# schematic.net
KiCad netlist of a schematic drawn in Altium Designer
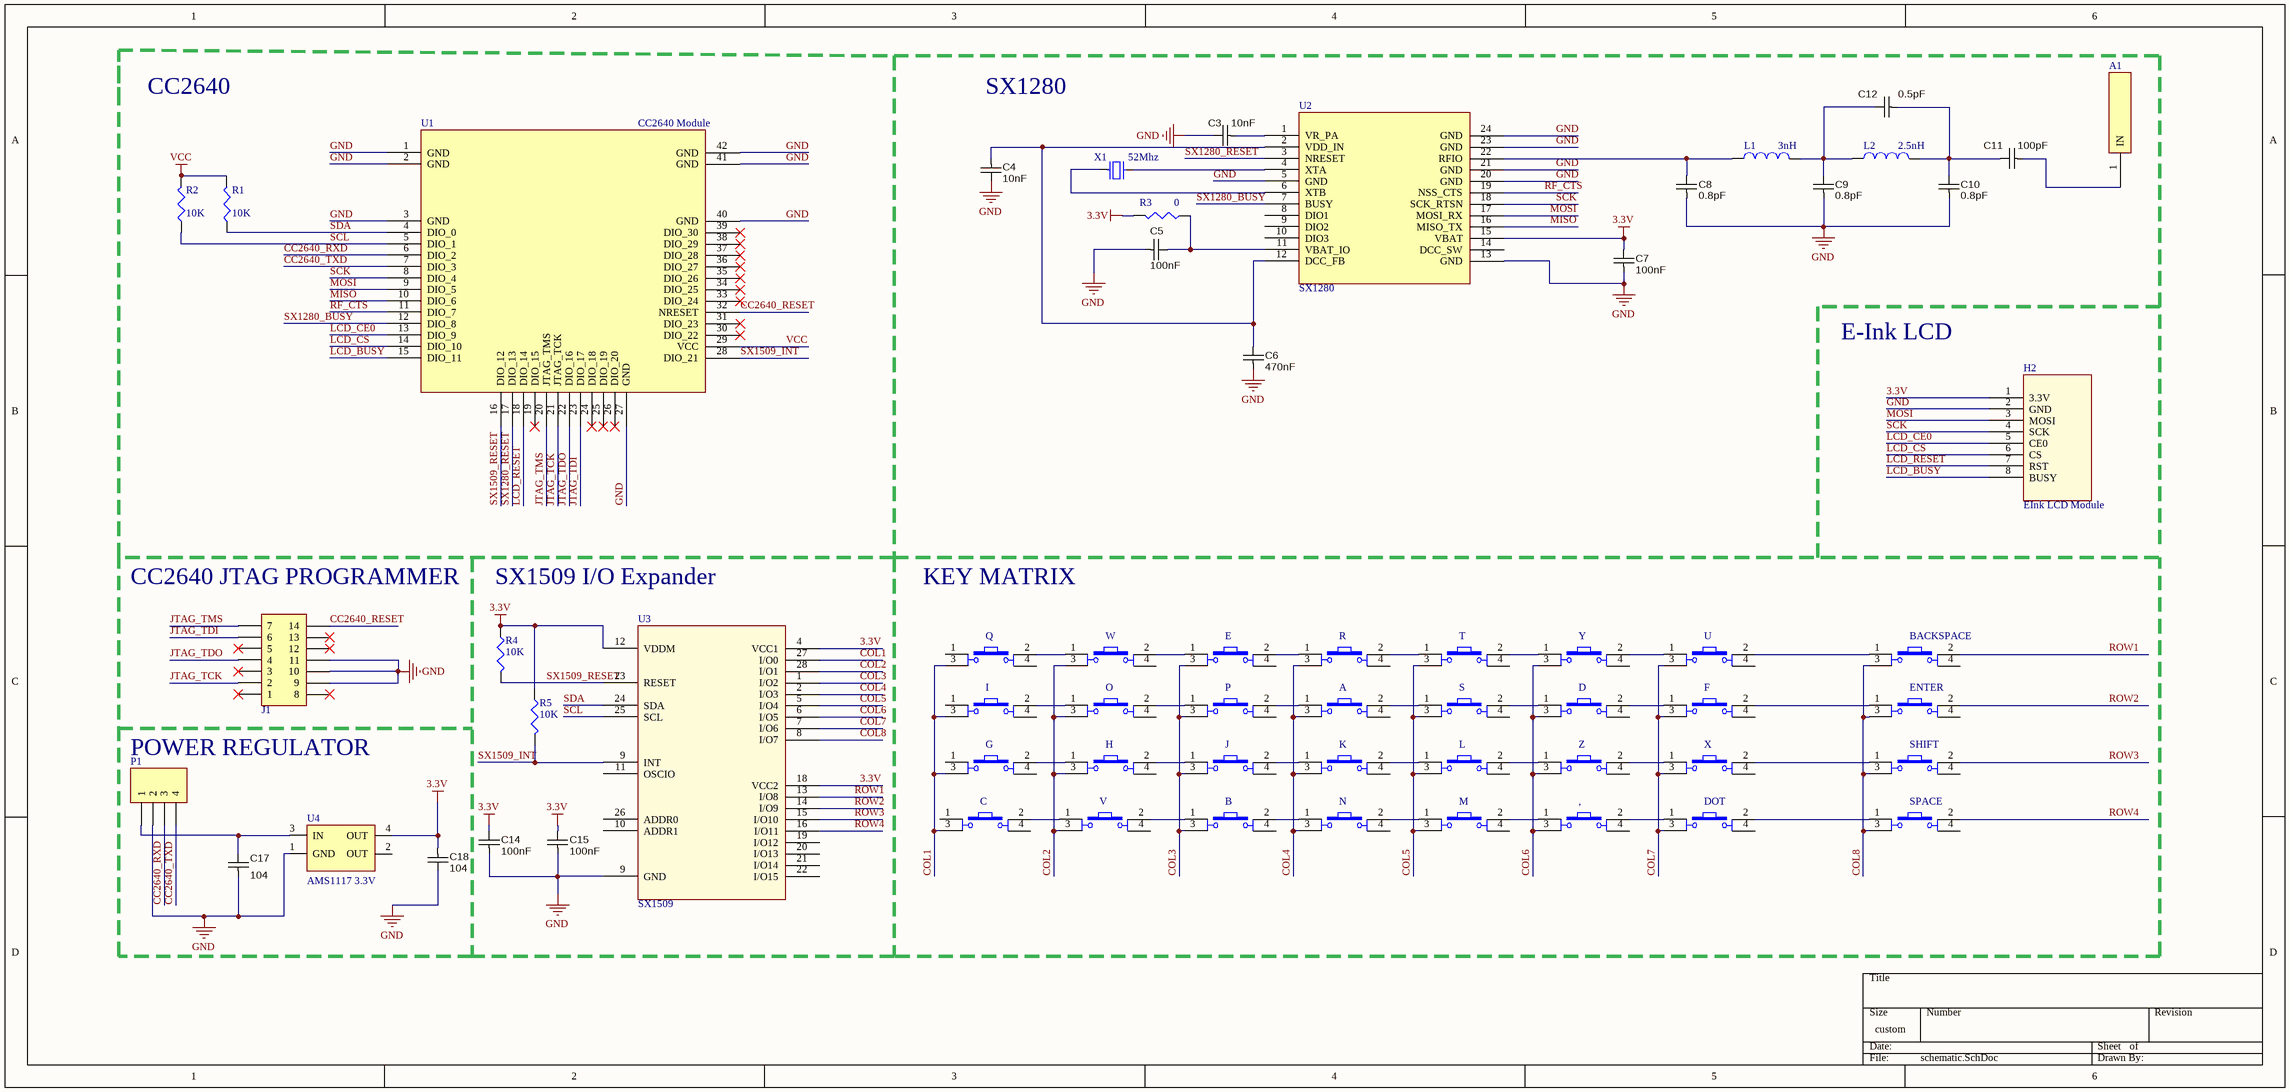
[diagram p0: schematic.SchDoc]

(export (version "E")
  (design (tool "Eeschema 10.0.6"))
  (components
    (comp (ref ",")
      (value "SW")
      (footprint "Kha_Button")
      (description "Switch button 4 pin")
      (libsource (lib "syhaunguyen") (part "SW4"))
    )
    (comp (ref "A")
      (value "SW")
      (footprint "Kha_Button")
      (description "Switch button 4 pin")
      (libsource (lib "syhaunguyen") (part "SW4"))
    )
    (comp (ref "A1")
      (value "Antenna")
      (footprint "Antenna")
      (libsource (lib "EInk_Project_Lib") (part "Antenna"))
    )
    (comp (ref "B")
      (value "SW")
      (footprint "Kha_Button")
      (description "Switch button 4 pin")
      (libsource (lib "syhaunguyen") (part "SW4"))
    )
    (comp (ref "BACKSPACE")
      (value "SW")
      (footprint "Kha_Button")
      (description "Switch button 4 pin")
      (libsource (lib "syhaunguyen") (part "SW4"))
    )
    (comp (ref "C")
      (value "SW")
      (footprint "Kha_Button")
      (description "Switch button 4 pin")
      (libsource (lib "syhaunguyen") (part "SW4"))
    )
    (comp (ref "C3")
      (value "10nF")
      (footprint "SMD-0603c")
      (description "Capacitor SMD Cer 1nF 10% 100V X7R 0603")
      (fields (field (name "TOLERANCE") "±10%") (field (name "Comment") "approved sub OK"))
      (libsource (lib "PBL - Capacitors") (part "CAPC_1n_0603_X7R_100V_10%"))
    )
    (comp (ref "C4")
      (value "10nF")
      (footprint "SMD-0603c")
      (description "Capacitor SMD Cer 1nF 10% 100V X7R 0603")
      (fields (field (name "TOLERANCE") "±10%") (field (name "Comment") "approved sub OK"))
      (libsource (lib "PBL - Capacitors") (part "CAPC_1n_0603_X7R_100V_10%"))
    )
    (comp (ref "C5")
      (value "100nF")
      (footprint "SMD-0603c")
      (description "Capacitor SMD Cer 1nF 10% 100V X7R 0603")
      (fields (field (name "TOLERANCE") "±10%") (field (name "Comment") "approved sub OK"))
      (libsource (lib "PBL - Capacitors") (part "CAPC_1n_0603_X7R_100V_10%"))
    )
    (comp (ref "C6")
      (value "470nF")
      (footprint "SMD-0603c")
      (description "Capacitor SMD Cer 1nF 10% 100V X7R 0603")
      (fields (field (name "TOLERANCE") "±10%") (field (name "Comment") "approved sub OK"))
      (libsource (lib "PBL - Capacitors") (part "CAPC_1n_0603_X7R_100V_10%"))
    )
    (comp (ref "C7")
      (value "100nF")
      (footprint "SMD-0603c")
      (description "Capacitor SMD Cer 1nF 10% 100V X7R 0603")
      (fields (field (name "TOLERANCE") "±10%") (field (name "Comment") "approved sub OK"))
      (libsource (lib "PBL - Capacitors") (part "CAPC_1n_0603_X7R_100V_10%"))
    )
    (comp (ref "C8")
      (value "0.8pF")
      (footprint "SMD-0603c")
      (description "Capacitor SMD Cer 1nF 10% 100V X7R 0603")
      (fields (field (name "TOLERANCE") "±10%") (field (name "Comment") "approved sub OK"))
      (libsource (lib "PBL - Capacitors") (part "CAPC_1n_0603_X7R_100V_10%"))
    )
    (comp (ref "C9")
      (value "0.8pF")
      (footprint "SMD-0603c")
      (description "Capacitor SMD Cer 1nF 10% 100V X7R 0603")
      (fields (field (name "TOLERANCE") "±10%") (field (name "Comment") "approved sub OK"))
      (libsource (lib "PBL - Capacitors") (part "CAPC_1n_0603_X7R_100V_10%"))
    )
    (comp (ref "C10")
      (value "0.8pF")
      (footprint "SMD-0603c")
      (description "Capacitor SMD Cer 1nF 10% 100V X7R 0603")
      (fields (field (name "TOLERANCE") "±10%") (field (name "Comment") "approved sub OK"))
      (libsource (lib "PBL - Capacitors") (part "CAPC_1n_0603_X7R_100V_10%"))
    )
    (comp (ref "C11")
      (value "100pF")
      (footprint "SMD-0603c")
      (description "Capacitor SMD Cer 1nF 10% 100V X7R 0603")
      (fields (field (name "TOLERANCE") "±10%") (field (name "Comment") "approved sub OK"))
      (libsource (lib "PBL - Capacitors") (part "CAPC_1n_0603_X7R_100V_10%"))
    )
    (comp (ref "C12")
      (value "0.5pF")
      (footprint "SMD-0603c")
      (description "Capacitor SMD Cer 1nF 10% 100V X7R 0603")
      (fields (field (name "TOLERANCE") "±10%") (field (name "Comment") "approved sub OK"))
      (libsource (lib "PBL - Capacitors") (part "CAPC_1n_0603_X7R_100V_10%"))
    )
    (comp (ref "C14")
      (value "100nF")
      (footprint "SMD-0603c")
      (description "Capacitor SMD Cer 1nF 10% 100V X7R 0603")
      (fields (field (name "TOLERANCE") "±10%") (field (name "Comment") "approved sub OK"))
      (libsource (lib "PBL - Capacitors") (part "CAPC_1n_0603_X7R_100V_10%"))
    )
    (comp (ref "C15")
      (value "100nF")
      (footprint "SMD-0603c")
      (description "Capacitor SMD Cer 1nF 10% 100V X7R 0603")
      (fields (field (name "TOLERANCE") "±10%") (field (name "Comment") "approved sub OK"))
      (libsource (lib "PBL - Capacitors") (part "CAPC_1n_0603_X7R_100V_10%"))
    )
    (comp (ref "C17")
      (value "104")
      (footprint "SMD-0603c")
      (description "Capacitor SMD Cer 1nF 10% 100V X7R 0603")
      (fields (field (name "TOLERANCE") "±10%") (field (name "Comment") "approved sub OK"))
      (libsource (lib "PBL - Capacitors") (part "CAPC_1n_0603_X7R_100V_10%"))
    )
    (comp (ref "C18")
      (value "104")
      (footprint "SMD-0603c")
      (description "Capacitor SMD Cer 1nF 10% 100V X7R 0603")
      (fields (field (name "TOLERANCE") "±10%") (field (name "Comment") "approved sub OK"))
      (libsource (lib "PBL - Capacitors") (part "CAPC_1n_0603_X7R_100V_10%"))
    )
    (comp (ref "D")
      (value "SW")
      (footprint "Kha_Button")
      (description "Switch button 4 pin")
      (libsource (lib "syhaunguyen") (part "SW4"))
    )
    (comp (ref "DOT")
      (value "SW")
      (footprint "Kha_Button")
      (description "Switch button 4 pin")
      (libsource (lib "syhaunguyen") (part "SW4"))
    )
    (comp (ref "E")
      (value "SW")
      (footprint "Kha_Button")
      (description "Switch button 4 pin")
      (libsource (lib "syhaunguyen") (part "SW4"))
    )
    (comp (ref "ENTER")
      (value "SW")
      (footprint "Kha_Button")
      (description "Switch button 4 pin")
      (libsource (lib "syhaunguyen") (part "SW4"))
    )
    (comp (ref "F")
      (value "SW")
      (footprint "Kha_Button")
      (description "Switch button 4 pin")
      (libsource (lib "syhaunguyen") (part "SW4"))
    )
    (comp (ref "G")
      (value "SW")
      (footprint "Kha_Button")
      (description "Switch button 4 pin")
      (libsource (lib "syhaunguyen") (part "SW4"))
    )
    (comp (ref "H")
      (value "SW")
      (footprint "Kha_Button")
      (description "Switch button 4 pin")
      (libsource (lib "syhaunguyen") (part "SW4"))
    )
    (comp (ref "H2")
      (value "EInk LCD Module")
      (footprint "EInk_Module")
      (libsource (lib "EInk_Project_Lib") (part "E-Ink LCD"))
    )
    (comp (ref "I")
      (value "SW")
      (footprint "Kha_Button")
      (description "Switch button 4 pin")
      (libsource (lib "syhaunguyen") (part "SW4"))
    )
    (comp (ref "J")
      (value "SW")
      (footprint "Kha_Button")
      (description "Switch button 4 pin")
      (libsource (lib "syhaunguyen") (part "SW4"))
    )
    (comp (ref "J1")
      (value "14p")
      (footprint "610114249121")
      (description "WR-PHD 2.54 mm Pin Header - SMT Type Double Row Right Angled, 14p")
      (fields (field (name "PARTNUMBER") "610114249121") (field (name "PUBLISHER") "Wurth Elektronik"))
      (libsource (lib "ALTIUM-PHD_2_54_SMT_DOUBLE_ROW_RIGHT_ANGLED_PIN_HEADER_6101XX249121-rev16c") (part "610114249121"))
    )
    (comp (ref "K")
      (value "SW")
      (footprint "Kha_Button")
      (description "Switch button 4 pin")
      (libsource (lib "syhaunguyen") (part "SW4"))
    )
    (comp (ref "L")
      (value "SW")
      (footprint "Kha_Button")
      (description "Switch button 4 pin")
      (libsource (lib "syhaunguyen") (part "SW4"))
    )
    (comp (ref "L1")
      (value "3nH")
      (footprint "0603")
      (description "Inductor")
      (fields (field (name "PUBLISHER") "Altium Limited"))
      (libsource (lib "Miscellaneous Devices") (part "Inductor"))
    )
    (comp (ref "L2")
      (value "2.5nH")
      (footprint "0603")
      (description "Inductor")
      (fields (field (name "PUBLISHER") "Altium Limited"))
      (libsource (lib "Miscellaneous Devices") (part "Inductor"))
    )
    (comp (ref "M")
      (value "SW")
      (footprint "Kha_Button")
      (description "Switch button 4 pin")
      (libsource (lib "syhaunguyen") (part "SW4"))
    )
    (comp (ref "N")
      (value "SW")
      (footprint "Kha_Button")
      (description "Switch button 4 pin")
      (libsource (lib "syhaunguyen") (part "SW4"))
    )
    (comp (ref "O")
      (value "SW")
      (footprint "Kha_Button")
      (description "Switch button 4 pin")
      (libsource (lib "syhaunguyen") (part "SW4"))
    )
    (comp (ref "P")
      (value "SW")
      (footprint "Kha_Button")
      (description "Switch button 4 pin")
      (libsource (lib "syhaunguyen") (part "SW4"))
    )
    (comp (ref "P1")
      (value "Header 4")
      (footprint "Header 4 SMT")
      (description "Header, 4-Pin")
      (fields (field (name "PUBLISHER") "Altium Limited"))
      (libsource (lib "Miscellaneous Connectors") (part "Header 4"))
    )
    (comp (ref "Q")
      (value "SW")
      (footprint "Kha_Button")
      (description "Switch button 4 pin")
      (libsource (lib "syhaunguyen") (part "SW4"))
    )
    (comp (ref "R")
      (value "SW")
      (footprint "Kha_Button")
      (description "Switch button 4 pin")
      (libsource (lib "syhaunguyen") (part "SW4"))
    )
    (comp (ref "R1")
      (value "10K")
      (footprint "J1-0603")
      (description "Resistor")
      (fields (field (name "Comment") "Res3") (field (name "PUBLISHER") "Altium Limited"))
      (libsource (lib "Miscellaneous Devices") (part "Res3"))
    )
    (comp (ref "R2")
      (value "10K")
      (footprint "J1-0603")
      (description "Resistor")
      (fields (field (name "Comment") "Res3") (field (name "PUBLISHER") "Altium Limited"))
      (libsource (lib "Miscellaneous Devices") (part "Res3"))
    )
    (comp (ref "R3")
      (value "0")
      (footprint "J1-0603")
      (description "Resistor")
      (fields (field (name "Comment") "Res3") (field (name "PUBLISHER") "Altium Limited"))
      (libsource (lib "Miscellaneous Devices") (part "Res3"))
    )
    (comp (ref "R4")
      (value "10K")
      (footprint "J1-0603")
      (description "Resistor")
      (fields (field (name "Comment") "Res3") (field (name "PUBLISHER") "Altium Limited"))
      (libsource (lib "Miscellaneous Devices") (part "Res3"))
    )
    (comp (ref "R5")
      (value "10K")
      (footprint "J1-0603")
      (description "Resistor")
      (fields (field (name "Comment") "Res3") (field (name "PUBLISHER") "Altium Limited"))
      (libsource (lib "Miscellaneous Devices") (part "Res3"))
    )
    (comp (ref "S")
      (value "SW")
      (footprint "Kha_Button")
      (description "Switch button 4 pin")
      (libsource (lib "syhaunguyen") (part "SW4"))
    )
    (comp (ref "SHIFT")
      (value "SW")
      (footprint "Kha_Button")
      (description "Switch button 4 pin")
      (libsource (lib "syhaunguyen") (part "SW4"))
    )
    (comp (ref "SPACE")
      (value "SW")
      (footprint "Kha_Button")
      (description "Switch button 4 pin")
      (libsource (lib "syhaunguyen") (part "SW4"))
    )
    (comp (ref "T")
      (value "SW")
      (footprint "Kha_Button")
      (description "Switch button 4 pin")
      (libsource (lib "syhaunguyen") (part "SW4"))
    )
    (comp (ref "U")
      (value "SW")
      (footprint "Kha_Button")
      (description "Switch button 4 pin")
      (libsource (lib "syhaunguyen") (part "SW4"))
    )
    (comp (ref "U1")
      (value "CC2640 Module")
      (footprint "CC2640 Module")
      (libsource (lib "EInk_Project_Lib") (part "CC2640 Module"))
    )
    (comp (ref "U2")
      (value "SX1280")
      (footprint "SX1280_QFN24 4x4")
      (libsource (lib "EInk_Project_Lib") (part "SX1280"))
    )
    (comp (ref "U3")
      (value "SX1509")
      (footprint "QFN28UT")
      (libsource (lib "EInk_Project_Lib") (part "SX1509"))
    )
    (comp (ref "U4")
      (value "AMS1117 3.3V")
      (footprint "AMS1117")
      (libsource (lib "EInk_Project_Lib") (part "AMS1117"))
    )
    (comp (ref "V")
      (value "SW")
      (footprint "Kha_Button")
      (description "Switch button 4 pin")
      (libsource (lib "syhaunguyen") (part "SW4"))
    )
    (comp (ref "W")
      (value "SW")
      (footprint "Kha_Button")
      (description "Switch button 4 pin")
      (libsource (lib "syhaunguyen") (part "SW4"))
    )
    (comp (ref "X")
      (value "SW")
      (footprint "Kha_Button")
      (description "Switch button 4 pin")
      (libsource (lib "syhaunguyen") (part "SW4"))
    )
    (comp (ref "X1")
      (value "52Mhz")
      (footprint "OSCSC500X320X110-4N")
      (description "Crystal For all Crystal 2pin.")
      (libsource (lib "syhaunguyen") (part "XT2"))
    )
    (comp (ref "Y")
      (value "SW")
      (footprint "Kha_Button")
      (description "Switch button 4 pin")
      (libsource (lib "syhaunguyen") (part "SW4"))
    )
    (comp (ref "Z")
      (value "SW")
      (footprint "Kha_Button")
      (description "Switch button 4 pin")
      (libsource (lib "syhaunguyen") (part "SW4"))
    )
  )
  (nets
    (net (code "1") (name "/CC2640_RESET") (class "Default")
      (node (ref "J1") (pin "14") (pinfunction "14_14") (pintype "passive"))
      (node (ref "U1") (pin "32") (pinfunction "NRESET_32") (pintype "passive"))
    )
    (net (code "2") (name "/CC2640_RXD") (class "Default")
      (node (ref "P1") (pin "3") (pinfunction "3_3") (pintype "passive"))
      (node (ref "U1") (pin "6") (pinfunction "DIO_2_6") (pintype "passive"))
    )
    (net (code "3") (name "/CC2640_TXD") (class "Default")
      (node (ref "P1") (pin "4") (pinfunction "4_4") (pintype "passive"))
      (node (ref "U1") (pin "7") (pinfunction "DIO_3_7") (pintype "passive"))
    )
    (net (code "4") (name "/COL1") (class "Default")
      (node (ref "C") (pin "3") (pintype "passive"))
      (node (ref "G") (pin "3") (pintype "passive"))
      (node (ref "I") (pin "3") (pintype "passive"))
      (node (ref "Q") (pin "3") (pintype "passive"))
      (node (ref "U3") (pin "27") (pinfunction "I/O0_27") (pintype "passive"))
    )
    (net (code "5") (name "/COL2") (class "Default")
      (node (ref "H") (pin "3") (pintype "passive"))
      (node (ref "O") (pin "3") (pintype "passive"))
      (node (ref "U3") (pin "28") (pinfunction "I/O1_28") (pintype "passive"))
      (node (ref "V") (pin "3") (pintype "passive"))
      (node (ref "W") (pin "3") (pintype "passive"))
    )
    (net (code "6") (name "/COL3") (class "Default")
      (node (ref "B") (pin "3") (pintype "passive"))
      (node (ref "E") (pin "3") (pintype "passive"))
      (node (ref "J") (pin "3") (pintype "passive"))
      (node (ref "P") (pin "3") (pintype "passive"))
      (node (ref "U3") (pin "1") (pinfunction "I/O2_1") (pintype "passive"))
    )
    (net (code "7") (name "/COL4") (class "Default")
      (node (ref "A") (pin "3") (pintype "passive"))
      (node (ref "K") (pin "3") (pintype "passive"))
      (node (ref "N") (pin "3") (pintype "passive"))
      (node (ref "R") (pin "3") (pintype "passive"))
      (node (ref "U3") (pin "2") (pinfunction "I/O3_2") (pintype "passive"))
    )
    (net (code "8") (name "/COL5") (class "Default")
      (node (ref "L") (pin "3") (pintype "passive"))
      (node (ref "M") (pin "3") (pintype "passive"))
      (node (ref "S") (pin "3") (pintype "passive"))
      (node (ref "T") (pin "3") (pintype "passive"))
      (node (ref "U3") (pin "5") (pinfunction "I/O4_5") (pintype "passive"))
    )
    (net (code "9") (name "/COL6") (class "Default")
      (node (ref ",") (pin "3") (pintype "passive"))
      (node (ref "D") (pin "3") (pintype "passive"))
      (node (ref "U3") (pin "6") (pinfunction "I/O5_6") (pintype "passive"))
      (node (ref "Y") (pin "3") (pintype "passive"))
      (node (ref "Z") (pin "3") (pintype "passive"))
    )
    (net (code "10") (name "/COL7") (class "Default")
      (node (ref "DOT") (pin "3") (pintype "passive"))
      (node (ref "F") (pin "3") (pintype "passive"))
      (node (ref "U") (pin "3") (pintype "passive"))
      (node (ref "U3") (pin "7") (pinfunction "I/O6_7") (pintype "passive"))
      (node (ref "X") (pin "3") (pintype "passive"))
    )
    (net (code "11") (name "/COL8") (class "Default")
      (node (ref "BACKSPACE") (pin "3") (pintype "passive"))
      (node (ref "ENTER") (pin "3") (pintype "passive"))
      (node (ref "SHIFT") (pin "3") (pintype "passive"))
      (node (ref "SPACE") (pin "3") (pintype "passive"))
      (node (ref "U3") (pin "8") (pinfunction "I/O7_8") (pintype "passive"))
    )
    (net (code "12") (name "/JTAG_TCK") (class "Default")
      (node (ref "J1") (pin "2") (pinfunction "2_2") (pintype "passive"))
      (node (ref "U1") (pin "21") (pinfunction "JTAG_TCK_21") (pintype "passive"))
    )
    (net (code "13") (name "/JTAG_TDI") (class "Default")
      (node (ref "J1") (pin "6") (pinfunction "6_6") (pintype "passive"))
      (node (ref "U1") (pin "23") (pinfunction "DIO_17_23") (pintype "passive"))
    )
    (net (code "14") (name "/JTAG_TDO") (class "Default")
      (node (ref "J1") (pin "4") (pinfunction "4_4") (pintype "passive"))
      (node (ref "U1") (pin "22") (pinfunction "DIO_16_22") (pintype "passive"))
    )
    (net (code "15") (name "/JTAG_TMS") (class "Default")
      (node (ref "J1") (pin "7") (pinfunction "7_7") (pintype "passive"))
      (node (ref "U1") (pin "20") (pinfunction "JTAG_TMS_20") (pintype "passive"))
    )
    (net (code "16") (name "/LCD_BUSY") (class "Default")
      (node (ref "H2") (pin "8") (pinfunction "BUSY_8") (pintype "passive"))
      (node (ref "U1") (pin "15") (pinfunction "DIO_11_15") (pintype "passive"))
    )
    (net (code "17") (name "/LCD_CE0") (class "Default")
      (node (ref "H2") (pin "5") (pinfunction "CE0_5") (pintype "passive"))
      (node (ref "U1") (pin "13") (pinfunction "DIO_9_13") (pintype "passive"))
    )
    (net (code "18") (name "/LCD_CS") (class "Default")
      (node (ref "H2") (pin "6") (pinfunction "CS_6") (pintype "passive"))
      (node (ref "U1") (pin "14") (pinfunction "DIO_10_14") (pintype "passive"))
    )
    (net (code "19") (name "/LCD_RESET") (class "Default")
      (node (ref "H2") (pin "7") (pinfunction "RST_7") (pintype "passive"))
      (node (ref "U1") (pin "18") (pinfunction "DIO_14_18") (pintype "passive"))
    )
    (net (code "20") (name "/MISO") (class "Default")
      (node (ref "U1") (pin "10") (pinfunction "DIO_6_10") (pintype "passive"))
      (node (ref "U2") (pin "16") (pinfunction "MISO_TX_16") (pintype "passive"))
    )
    (net (code "21") (name "/MOSI") (class "Default")
      (node (ref "H2") (pin "3") (pinfunction "MOSI_3") (pintype "passive"))
      (node (ref "U1") (pin "9") (pinfunction "DIO_5_9") (pintype "passive"))
      (node (ref "U2") (pin "17") (pinfunction "MOSI_RX_17") (pintype "passive"))
    )
    (net (code "22") (name "/RF_CTS") (class "Default")
      (node (ref "U1") (pin "11") (pinfunction "DIO_7_11") (pintype "passive"))
      (node (ref "U2") (pin "19") (pinfunction "NSS_CTS_19") (pintype "passive"))
    )
    (net (code "23") (name "/ROW1") (class "Default")
      (node (ref "BACKSPACE") (pin "2") (pintype "passive"))
      (node (ref "U3") (pin "13") (pinfunction "I/O8_13") (pintype "passive"))
    )
    (net (code "24") (name "/ROW2") (class "Default")
      (node (ref "ENTER") (pin "2") (pintype "passive"))
      (node (ref "U3") (pin "14") (pinfunction "I/O9_14") (pintype "passive"))
    )
    (net (code "25") (name "/ROW3") (class "Default")
      (node (ref "SHIFT") (pin "2") (pintype "passive"))
      (node (ref "U3") (pin "15") (pinfunction "I/O10_15") (pintype "passive"))
    )
    (net (code "26") (name "/ROW4") (class "Default")
      (node (ref "SPACE") (pin "2") (pintype "passive"))
      (node (ref "U3") (pin "16") (pinfunction "I/O11_16") (pintype "passive"))
    )
    (net (code "27") (name "/SCK") (class "Default")
      (node (ref "H2") (pin "4") (pinfunction "SCK_4") (pintype "passive"))
      (node (ref "U1") (pin "8") (pinfunction "DIO_4_8") (pintype "passive"))
      (node (ref "U2") (pin "18") (pinfunction "SCK_RTSN_18") (pintype "passive"))
    )
    (net (code "28") (name "/SCL") (class "Default")
      (node (ref "R2") (pin "1") (pinfunction "1_1") (pintype "passive"))
      (node (ref "U1") (pin "5") (pinfunction "DIO_1_5") (pintype "passive"))
      (node (ref "U3") (pin "25") (pinfunction "SCL_25") (pintype "passive"))
    )
    (net (code "29") (name "/SDA") (class "Default")
      (node (ref "R1") (pin "1") (pinfunction "1_1") (pintype "passive"))
      (node (ref "U1") (pin "4") (pinfunction "DIO_0_4") (pintype "passive"))
      (node (ref "U3") (pin "24") (pinfunction "SDA_24") (pintype "passive"))
    )
    (net (code "30") (name "/SX1280_BUSY") (class "Default")
      (node (ref "U1") (pin "12") (pinfunction "DIO_8_12") (pintype "passive"))
      (node (ref "U2") (pin "7") (pinfunction "BUSY_7") (pintype "passive"))
    )
    (net (code "31") (name "/SX1280_RESET") (class "Default")
      (node (ref "U1") (pin "17") (pinfunction "DIO_13_17") (pintype "passive"))
      (node (ref "U2") (pin "3") (pinfunction "NRESET_3") (pintype "passive"))
    )
    (net (code "32") (name "/SX1509_INT") (class "Default")
      (node (ref "R5") (pin "2") (pinfunction "2_2") (pintype "passive"))
      (node (ref "U1") (pin "28") (pinfunction "DIO_21_28") (pintype "passive"))
      (node (ref "U3") (pin "9") (pinfunction "INT_9") (pintype "passive"))
    )
    (net (code "33") (name "/SX1509_RESET") (class "Default")
      (node (ref "R4") (pin "2") (pinfunction "2_2") (pintype "passive"))
      (node (ref "U1") (pin "16") (pinfunction "DIO_12_16") (pintype "passive"))
      (node (ref "U3") (pin "23") (pinfunction "RESET_23") (pintype "passive"))
    )
    (net (code "34") (name "3.3V") (class "Default")
      (node (ref "C14") (pin "2") (pintype "passive"))
      (node (ref "C15") (pin "2") (pintype "passive"))
      (node (ref "C18") (pin "1") (pintype "passive"))
      (node (ref "C7") (pin "2") (pintype "passive"))
      (node (ref "H2") (pin "1") (pinfunction "3.3V_1") (pintype "passive"))
      (node (ref "R3") (pin "2") (pinfunction "2_2") (pintype "passive"))
      (node (ref "R4") (pin "1") (pinfunction "1_1") (pintype "passive"))
      (node (ref "R5") (pin "1") (pinfunction "1_1") (pintype "passive"))
      (node (ref "U2") (pin "15") (pinfunction "VBAT_15") (pintype "passive"))
      (node (ref "U3") (pin "12") (pinfunction "VDDM_12") (pintype "passive"))
      (node (ref "U3") (pin "18") (pinfunction "VCC2_18") (pintype "passive"))
      (node (ref "U3") (pin "4") (pinfunction "VCC1_4") (pintype "passive"))
      (node (ref "U4") (pin "4") (pinfunction "OUT_4") (pintype "passive"))
    )
    (net (code "35") (name "GND") (class "Default")
      (node (ref "C10") (pin "1") (pintype "passive"))
      (node (ref "C14") (pin "1") (pintype "passive"))
      (node (ref "C15") (pin "1") (pintype "passive"))
      (node (ref "C17") (pin "1") (pintype "passive"))
      (node (ref "C18") (pin "2") (pintype "passive"))
      (node (ref "C3") (pin "2") (pintype "passive"))
      (node (ref "C4") (pin "2") (pintype "passive"))
      (node (ref "C5") (pin "1") (pintype "passive"))
      (node (ref "C6") (pin "1") (pintype "passive"))
      (node (ref "C7") (pin "1") (pintype "passive"))
      (node (ref "C8") (pin "1") (pintype "passive"))
      (node (ref "C9") (pin "1") (pintype "passive"))
      (node (ref "H2") (pin "2") (pinfunction "GND_2") (pintype "passive"))
      (node (ref "J1") (pin "10") (pinfunction "10_10") (pintype "passive"))
      (node (ref "J1") (pin "11") (pinfunction "11_11") (pintype "passive"))
      (node (ref "J1") (pin "9") (pinfunction "9_9") (pintype "passive"))
      (node (ref "P1") (pin "2") (pinfunction "2_2") (pintype "passive"))
      (node (ref "U1") (pin "1") (pinfunction "GND_1") (pintype "passive"))
      (node (ref "U1") (pin "2") (pinfunction "GND_2") (pintype "passive"))
      (node (ref "U1") (pin "27") (pinfunction "GND_27") (pintype "passive"))
      (node (ref "U1") (pin "3") (pinfunction "GND_3") (pintype "passive"))
      (node (ref "U1") (pin "40") (pinfunction "GND_40") (pintype "passive"))
      (node (ref "U1") (pin "41") (pinfunction "GND_41") (pintype "passive"))
      (node (ref "U1") (pin "42") (pinfunction "GND_42") (pintype "passive"))
      (node (ref "U2") (pin "13") (pinfunction "GND_13") (pintype "passive"))
      (node (ref "U2") (pin "20") (pinfunction "GND_20") (pintype "passive"))
      (node (ref "U2") (pin "21") (pinfunction "GND_21") (pintype "passive"))
      (node (ref "U2") (pin "23") (pinfunction "GND_23") (pintype "passive"))
      (node (ref "U2") (pin "24") (pinfunction "GND_24") (pintype "passive"))
      (node (ref "U2") (pin "5") (pinfunction "GND_5") (pintype "passive"))
      (node (ref "U3") (pin "9") (pinfunction "GND_9") (pintype "passive"))
      (node (ref "U4") (pin "1") (pinfunction "GND_1") (pintype "passive"))
    )
    (net (code "36") (name "Net-(,-Pad1)") (class "Default")
      (node (ref ",") (pin "1") (pintype "passive"))
      (node (ref "M") (pin "2") (pintype "passive"))
    )
    (net (code "37") (name "Net-(,-Pad2)") (class "Default")
      (node (ref ",") (pin "2") (pintype "passive"))
      (node (ref "DOT") (pin "1") (pintype "passive"))
    )
    (net (code "38") (name "Net-(A-Pad1)") (class "Default")
      (node (ref "A") (pin "1") (pintype "passive"))
      (node (ref "P") (pin "2") (pintype "passive"))
    )
    (net (code "39") (name "Net-(A-Pad2)") (class "Default")
      (node (ref "A") (pin "2") (pintype "passive"))
      (node (ref "S") (pin "1") (pintype "passive"))
    )
    (net (code "40") (name "Net-(A1-IN)") (class "Default")
      (node (ref "A1") (pin "1") (pinfunction "IN_1") (pintype "passive"))
      (node (ref "C11") (pin "1") (pintype "passive"))
    )
    (net (code "41") (name "Net-(B-Pad1)") (class "Default")
      (node (ref "B") (pin "1") (pintype "passive"))
      (node (ref "V") (pin "2") (pintype "passive"))
    )
    (net (code "42") (name "Net-(B-Pad2)") (class "Default")
      (node (ref "B") (pin "2") (pintype "passive"))
      (node (ref "N") (pin "1") (pintype "passive"))
    )
    (net (code "43") (name "Net-(BACKSPACE-Pad1)") (class "Default")
      (node (ref "BACKSPACE") (pin "1") (pintype "passive"))
      (node (ref "U") (pin "2") (pintype "passive"))
    )
    (net (code "44") (name "Net-(C-Pad2)") (class "Default")
      (node (ref "C") (pin "2") (pintype "passive"))
      (node (ref "V") (pin "1") (pintype "passive"))
    )
    (net (code "45") (name "Net-(C10-Pad2)") (class "Default")
      (node (ref "C10") (pin "2") (pintype "passive"))
      (node (ref "C11") (pin "2") (pintype "passive"))
      (node (ref "C12") (pin "1") (pintype "passive"))
      (node (ref "L2") (pin "2") (pinfunction "2_2") (pintype "passive"))
    )
    (net (code "46") (name "Net-(C12-Pad2)") (class "Default")
      (node (ref "C12") (pin "2") (pintype "passive"))
      (node (ref "C9") (pin "2") (pintype "passive"))
      (node (ref "L1") (pin "2") (pinfunction "2_2") (pintype "passive"))
      (node (ref "L2") (pin "1") (pinfunction "1_1") (pintype "passive"))
    )
    (net (code "47") (name "Net-(D-Pad1)") (class "Default")
      (node (ref "D") (pin "1") (pintype "passive"))
      (node (ref "S") (pin "2") (pintype "passive"))
    )
    (net (code "48") (name "Net-(D-Pad2)") (class "Default")
      (node (ref "D") (pin "2") (pintype "passive"))
      (node (ref "F") (pin "1") (pintype "passive"))
    )
    (net (code "49") (name "Net-(DOT-Pad2)") (class "Default")
      (node (ref "DOT") (pin "2") (pintype "passive"))
      (node (ref "SPACE") (pin "1") (pintype "passive"))
    )
    (net (code "50") (name "Net-(E-Pad1)") (class "Default")
      (node (ref "E") (pin "1") (pintype "passive"))
      (node (ref "W") (pin "2") (pintype "passive"))
    )
    (net (code "51") (name "Net-(E-Pad2)") (class "Default")
      (node (ref "E") (pin "2") (pintype "passive"))
      (node (ref "R") (pin "1") (pintype "passive"))
    )
    (net (code "52") (name "Net-(ENTER-Pad1)") (class "Default")
      (node (ref "ENTER") (pin "1") (pintype "passive"))
      (node (ref "F") (pin "2") (pintype "passive"))
    )
    (net (code "53") (name "Net-(G-Pad2)") (class "Default")
      (node (ref "G") (pin "2") (pintype "passive"))
      (node (ref "H") (pin "1") (pintype "passive"))
    )
    (net (code "54") (name "Net-(H-Pad2)") (class "Default")
      (node (ref "H") (pin "2") (pintype "passive"))
      (node (ref "J") (pin "1") (pintype "passive"))
    )
    (net (code "55") (name "Net-(I-Pad2)") (class "Default")
      (node (ref "I") (pin "2") (pintype "passive"))
      (node (ref "O") (pin "1") (pintype "passive"))
    )
    (net (code "56") (name "Net-(J-Pad2)") (class "Default")
      (node (ref "J") (pin "2") (pintype "passive"))
      (node (ref "K") (pin "1") (pintype "passive"))
    )
    (net (code "57") (name "Net-(K-Pad2)") (class "Default")
      (node (ref "K") (pin "2") (pintype "passive"))
      (node (ref "L") (pin "1") (pintype "passive"))
    )
    (net (code "58") (name "Net-(L-Pad2)") (class "Default")
      (node (ref "L") (pin "2") (pintype "passive"))
      (node (ref "Z") (pin "1") (pintype "passive"))
    )
    (net (code "59") (name "Net-(M-Pad1)") (class "Default")
      (node (ref "M") (pin "1") (pintype "passive"))
      (node (ref "N") (pin "2") (pintype "passive"))
    )
    (net (code "60") (name "Net-(O-Pad2)") (class "Default")
      (node (ref "O") (pin "2") (pintype "passive"))
      (node (ref "P") (pin "1") (pintype "passive"))
    )
    (net (code "61") (name "Net-(Q-Pad2)") (class "Default")
      (node (ref "Q") (pin "2") (pintype "passive"))
      (node (ref "W") (pin "1") (pintype "passive"))
    )
    (net (code "62") (name "Net-(R-Pad2)") (class "Default")
      (node (ref "R") (pin "2") (pintype "passive"))
      (node (ref "T") (pin "1") (pintype "passive"))
    )
    (net (code "63") (name "Net-(SHIFT-Pad1)") (class "Default")
      (node (ref "SHIFT") (pin "1") (pintype "passive"))
      (node (ref "X") (pin "2") (pintype "passive"))
    )
    (net (code "64") (name "Net-(T-Pad2)") (class "Default")
      (node (ref "T") (pin "2") (pintype "passive"))
      (node (ref "Y") (pin "1") (pintype "passive"))
    )
    (net (code "65") (name "Net-(U-Pad1)") (class "Default")
      (node (ref "U") (pin "1") (pintype "passive"))
      (node (ref "Y") (pin "2") (pintype "passive"))
    )
    (net (code "66") (name "Net-(U2-DCC_FB)") (class "Default")
      (node (ref "C4") (pin "1") (pintype "passive"))
      (node (ref "C6") (pin "2") (pintype "passive"))
      (node (ref "U2") (pin "12") (pinfunction "DCC_FB_12") (pintype "passive"))
      (node (ref "U2") (pin "2") (pinfunction "VDD_IN_2") (pintype "passive"))
    )
    (net (code "67") (name "Net-(U2-RFIO)") (class "Default")
      (node (ref "C8") (pin "2") (pintype "passive"))
      (node (ref "L1") (pin "1") (pinfunction "1_1") (pintype "passive"))
      (node (ref "U2") (pin "22") (pinfunction "RFIO_22") (pintype "passive"))
    )
    (net (code "68") (name "Net-(U2-VBAT_IO)") (class "Default")
      (node (ref "C5") (pin "2") (pintype "passive"))
      (node (ref "R3") (pin "1") (pinfunction "1_1") (pintype "passive"))
      (node (ref "U2") (pin "11") (pinfunction "VBAT_IO_11") (pintype "passive"))
    )
    (net (code "69") (name "Net-(U2-VR_PA)") (class "Default")
      (node (ref "C3") (pin "1") (pintype "passive"))
      (node (ref "U2") (pin "1") (pinfunction "VR_PA_1") (pintype "passive"))
    )
    (net (code "70") (name "Net-(U2-XTA)") (class "Default")
      (node (ref "U2") (pin "4") (pinfunction "XTA_4") (pintype "passive"))
      (node (ref "X1") (pin "3") (pinfunction "2_3") (pintype "passive"))
    )
    (net (code "71") (name "Net-(U2-XTB)") (class "Default")
      (node (ref "U2") (pin "6") (pinfunction "XTB_6") (pintype "passive"))
      (node (ref "X1") (pin "1") (pinfunction "1_1") (pintype "passive"))
    )
    (net (code "72") (name "Net-(U4-IN)") (class "Default")
      (node (ref "C17") (pin "2") (pintype "passive"))
      (node (ref "P1") (pin "1") (pinfunction "1_1") (pintype "passive"))
      (node (ref "U4") (pin "3") (pinfunction "IN_3") (pintype "passive"))
    )
    (net (code "73") (name "Net-(X-Pad1)") (class "Default")
      (node (ref "X") (pin "1") (pintype "passive"))
      (node (ref "Z") (pin "2") (pintype "passive"))
    )
    (net (code "74") (name "VCC") (class "Default")
      (node (ref "R1") (pin "2") (pinfunction "2_2") (pintype "passive"))
      (node (ref "R2") (pin "2") (pinfunction "2_2") (pintype "passive"))
      (node (ref "U1") (pin "29") (pinfunction "VCC_29") (pintype "passive"))
    )
    (net (code "75") (name "unconnected-(,-Pad4)") (class "Default")
      (node (ref ",") (pin "4") (pintype "passive"))
    )
    (net (code "76") (name "unconnected-(A-Pad4)") (class "Default")
      (node (ref "A") (pin "4") (pintype "passive"))
    )
    (net (code "77") (name "unconnected-(B-Pad4)") (class "Default")
      (node (ref "B") (pin "4") (pintype "passive"))
    )
    (net (code "78") (name "unconnected-(BACKSPACE-Pad4)") (class "Default")
      (node (ref "BACKSPACE") (pin "4") (pintype "passive"))
    )
    (net (code "79") (name "unconnected-(C-Pad1)") (class "Default")
      (node (ref "C") (pin "1") (pintype "passive"))
    )
    (net (code "80") (name "unconnected-(C-Pad4)") (class "Default")
      (node (ref "C") (pin "4") (pintype "passive"))
    )
    (net (code "81") (name "unconnected-(D-Pad4)") (class "Default")
      (node (ref "D") (pin "4") (pintype "passive"))
    )
    (net (code "82") (name "unconnected-(DOT-Pad4)") (class "Default")
      (node (ref "DOT") (pin "4") (pintype "passive"))
    )
    (net (code "83") (name "unconnected-(E-Pad4)") (class "Default")
      (node (ref "E") (pin "4") (pintype "passive"))
    )
    (net (code "84") (name "unconnected-(ENTER-Pad4)") (class "Default")
      (node (ref "ENTER") (pin "4") (pintype "passive"))
    )
    (net (code "85") (name "unconnected-(F-Pad4)") (class "Default")
      (node (ref "F") (pin "4") (pintype "passive"))
    )
    (net (code "86") (name "unconnected-(G-Pad1)") (class "Default")
      (node (ref "G") (pin "1") (pintype "passive"))
    )
    (net (code "87") (name "unconnected-(G-Pad4)") (class "Default")
      (node (ref "G") (pin "4") (pintype "passive"))
    )
    (net (code "88") (name "unconnected-(H-Pad4)") (class "Default")
      (node (ref "H") (pin "4") (pintype "passive"))
    )
    (net (code "89") (name "unconnected-(I-Pad1)") (class "Default")
      (node (ref "I") (pin "1") (pintype "passive"))
    )
    (net (code "90") (name "unconnected-(I-Pad4)") (class "Default")
      (node (ref "I") (pin "4") (pintype "passive"))
    )
    (net (code "91") (name "unconnected-(J-Pad4)") (class "Default")
      (node (ref "J") (pin "4") (pintype "passive"))
    )
    (net (code "92") (name "unconnected-(J1-Pad1)") (class "Default")
      (node (ref "J1") (pin "1") (pinfunction "1_1") (pintype "passive+no_connect"))
    )
    (net (code "93") (name "unconnected-(J1-Pad3)") (class "Default")
      (node (ref "J1") (pin "3") (pinfunction "3_3") (pintype "passive+no_connect"))
    )
    (net (code "94") (name "unconnected-(J1-Pad5)") (class "Default")
      (node (ref "J1") (pin "5") (pinfunction "5_5") (pintype "passive+no_connect"))
    )
    (net (code "95") (name "unconnected-(J1-Pad8)") (class "Default")
      (node (ref "J1") (pin "8") (pinfunction "8_8") (pintype "passive+no_connect"))
    )
    (net (code "96") (name "unconnected-(J1-Pad12)") (class "Default")
      (node (ref "J1") (pin "12") (pinfunction "12_12") (pintype "passive+no_connect"))
    )
    (net (code "97") (name "unconnected-(J1-Pad13)") (class "Default")
      (node (ref "J1") (pin "13") (pinfunction "13_13") (pintype "passive+no_connect"))
    )
    (net (code "98") (name "unconnected-(K-Pad4)") (class "Default")
      (node (ref "K") (pin "4") (pintype "passive"))
    )
    (net (code "99") (name "unconnected-(L-Pad4)") (class "Default")
      (node (ref "L") (pin "4") (pintype "passive"))
    )
    (net (code "100") (name "unconnected-(M-Pad4)") (class "Default")
      (node (ref "M") (pin "4") (pintype "passive"))
    )
    (net (code "101") (name "unconnected-(N-Pad4)") (class "Default")
      (node (ref "N") (pin "4") (pintype "passive"))
    )
    (net (code "102") (name "unconnected-(O-Pad4)") (class "Default")
      (node (ref "O") (pin "4") (pintype "passive"))
    )
    (net (code "103") (name "unconnected-(P-Pad4)") (class "Default")
      (node (ref "P") (pin "4") (pintype "passive"))
    )
    (net (code "104") (name "unconnected-(Q-Pad1)") (class "Default")
      (node (ref "Q") (pin "1") (pintype "passive"))
    )
    (net (code "105") (name "unconnected-(Q-Pad4)") (class "Default")
      (node (ref "Q") (pin "4") (pintype "passive"))
    )
    (net (code "106") (name "unconnected-(R-Pad4)") (class "Default")
      (node (ref "R") (pin "4") (pintype "passive"))
    )
    (net (code "107") (name "unconnected-(S-Pad4)") (class "Default")
      (node (ref "S") (pin "4") (pintype "passive"))
    )
    (net (code "108") (name "unconnected-(SHIFT-Pad4)") (class "Default")
      (node (ref "SHIFT") (pin "4") (pintype "passive"))
    )
    (net (code "109") (name "unconnected-(SPACE-Pad4)") (class "Default")
      (node (ref "SPACE") (pin "4") (pintype "passive"))
    )
    (net (code "110") (name "unconnected-(T-Pad4)") (class "Default")
      (node (ref "T") (pin "4") (pintype "passive"))
    )
    (net (code "111") (name "unconnected-(U-Pad4)") (class "Default")
      (node (ref "U") (pin "4") (pintype "passive"))
    )
    (net (code "112") (name "unconnected-(U1-DIO_15-Pad19)") (class "Default")
      (node (ref "U1") (pin "19") (pinfunction "DIO_15_19") (pintype "passive+no_connect"))
    )
    (net (code "113") (name "unconnected-(U1-DIO_18-Pad24)") (class "Default")
      (node (ref "U1") (pin "24") (pinfunction "DIO_18_24") (pintype "passive+no_connect"))
    )
    (net (code "114") (name "unconnected-(U1-DIO_19-Pad25)") (class "Default")
      (node (ref "U1") (pin "25") (pinfunction "DIO_19_25") (pintype "passive+no_connect"))
    )
    (net (code "115") (name "unconnected-(U1-DIO_20-Pad26)") (class "Default")
      (node (ref "U1") (pin "26") (pinfunction "DIO_20_26") (pintype "passive+no_connect"))
    )
    (net (code "116") (name "unconnected-(U1-DIO_22-Pad30)") (class "Default")
      (node (ref "U1") (pin "30") (pinfunction "DIO_22_30") (pintype "passive+no_connect"))
    )
    (net (code "117") (name "unconnected-(U1-DIO_23-Pad31)") (class "Default")
      (node (ref "U1") (pin "31") (pinfunction "DIO_23_31") (pintype "passive+no_connect"))
    )
    (net (code "118") (name "unconnected-(U1-DIO_24-Pad33)") (class "Default")
      (node (ref "U1") (pin "33") (pinfunction "DIO_24_33") (pintype "passive+no_connect"))
    )
    (net (code "119") (name "unconnected-(U1-DIO_25-Pad34)") (class "Default")
      (node (ref "U1") (pin "34") (pinfunction "DIO_25_34") (pintype "passive+no_connect"))
    )
    (net (code "120") (name "unconnected-(U1-DIO_26-Pad35)") (class "Default")
      (node (ref "U1") (pin "35") (pinfunction "DIO_26_35") (pintype "passive+no_connect"))
    )
    (net (code "121") (name "unconnected-(U1-DIO_27-Pad36)") (class "Default")
      (node (ref "U1") (pin "36") (pinfunction "DIO_27_36") (pintype "passive+no_connect"))
    )
    (net (code "122") (name "unconnected-(U1-DIO_28-Pad37)") (class "Default")
      (node (ref "U1") (pin "37") (pinfunction "DIO_28_37") (pintype "passive+no_connect"))
    )
    (net (code "123") (name "unconnected-(U1-DIO_29-Pad38)") (class "Default")
      (node (ref "U1") (pin "38") (pinfunction "DIO_29_38") (pintype "passive+no_connect"))
    )
    (net (code "124") (name "unconnected-(U1-DIO_30-Pad39)") (class "Default")
      (node (ref "U1") (pin "39") (pinfunction "DIO_30_39") (pintype "passive+no_connect"))
    )
    (net (code "125") (name "unconnected-(U2-DCC_SW-Pad14)") (class "Default")
      (node (ref "U2") (pin "14") (pinfunction "DCC_SW_14") (pintype "passive"))
    )
    (net (code "126") (name "unconnected-(U2-DIO1-Pad8)") (class "Default")
      (node (ref "U2") (pin "8") (pinfunction "DIO1_8") (pintype "passive"))
    )
    (net (code "127") (name "unconnected-(U2-DIO2-Pad9)") (class "Default")
      (node (ref "U2") (pin "9") (pinfunction "DIO2_9") (pintype "passive"))
    )
    (net (code "128") (name "unconnected-(U2-DIO3-Pad10)") (class "Default")
      (node (ref "U2") (pin "10") (pinfunction "DIO3_10") (pintype "passive"))
    )
    (net (code "129") (name "unconnected-(U3-ADDR0-Pad26)") (class "Default")
      (node (ref "U3") (pin "26") (pinfunction "ADDR0_26") (pintype "passive"))
    )
    (net (code "130") (name "unconnected-(U3-ADDR1-Pad10)") (class "Default")
      (node (ref "U3") (pin "10") (pinfunction "ADDR1_10") (pintype "passive"))
    )
    (net (code "131") (name "unconnected-(U3-I{slash}O12-Pad19)") (class "Default")
      (node (ref "U3") (pin "19") (pinfunction "I/O12_19") (pintype "passive"))
    )
    (net (code "132") (name "unconnected-(U3-I{slash}O13-Pad20)") (class "Default")
      (node (ref "U3") (pin "20") (pinfunction "I/O13_20") (pintype "passive"))
    )
    (net (code "133") (name "unconnected-(U3-I{slash}O14-Pad21)") (class "Default")
      (node (ref "U3") (pin "21") (pinfunction "I/O14_21") (pintype "passive"))
    )
    (net (code "134") (name "unconnected-(U3-I{slash}O15-Pad22)") (class "Default")
      (node (ref "U3") (pin "22") (pinfunction "I/O15_22") (pintype "passive"))
    )
    (net (code "135") (name "unconnected-(U3-OSCIO-Pad11)") (class "Default")
      (node (ref "U3") (pin "11") (pinfunction "OSCIO_11") (pintype "passive"))
    )
    (net (code "136") (name "unconnected-(U4-OUT-Pad2)") (class "Default")
      (node (ref "U4") (pin "2") (pinfunction "OUT_2") (pintype "passive"))
    )
    (net (code "137") (name "unconnected-(V-Pad4)") (class "Default")
      (node (ref "V") (pin "4") (pintype "passive"))
    )
    (net (code "138") (name "unconnected-(W-Pad4)") (class "Default")
      (node (ref "W") (pin "4") (pintype "passive"))
    )
    (net (code "139") (name "unconnected-(X-Pad4)") (class "Default")
      (node (ref "X") (pin "4") (pintype "passive"))
    )
    (net (code "140") (name "unconnected-(Y-Pad4)") (class "Default")
      (node (ref "Y") (pin "4") (pintype "passive"))
    )
    (net (code "141") (name "unconnected-(Z-Pad4)") (class "Default")
      (node (ref "Z") (pin "4") (pintype "passive"))
    )
  )
)
